# logic-level.net
KiCad netlist of a schematic drawn in EAGLE
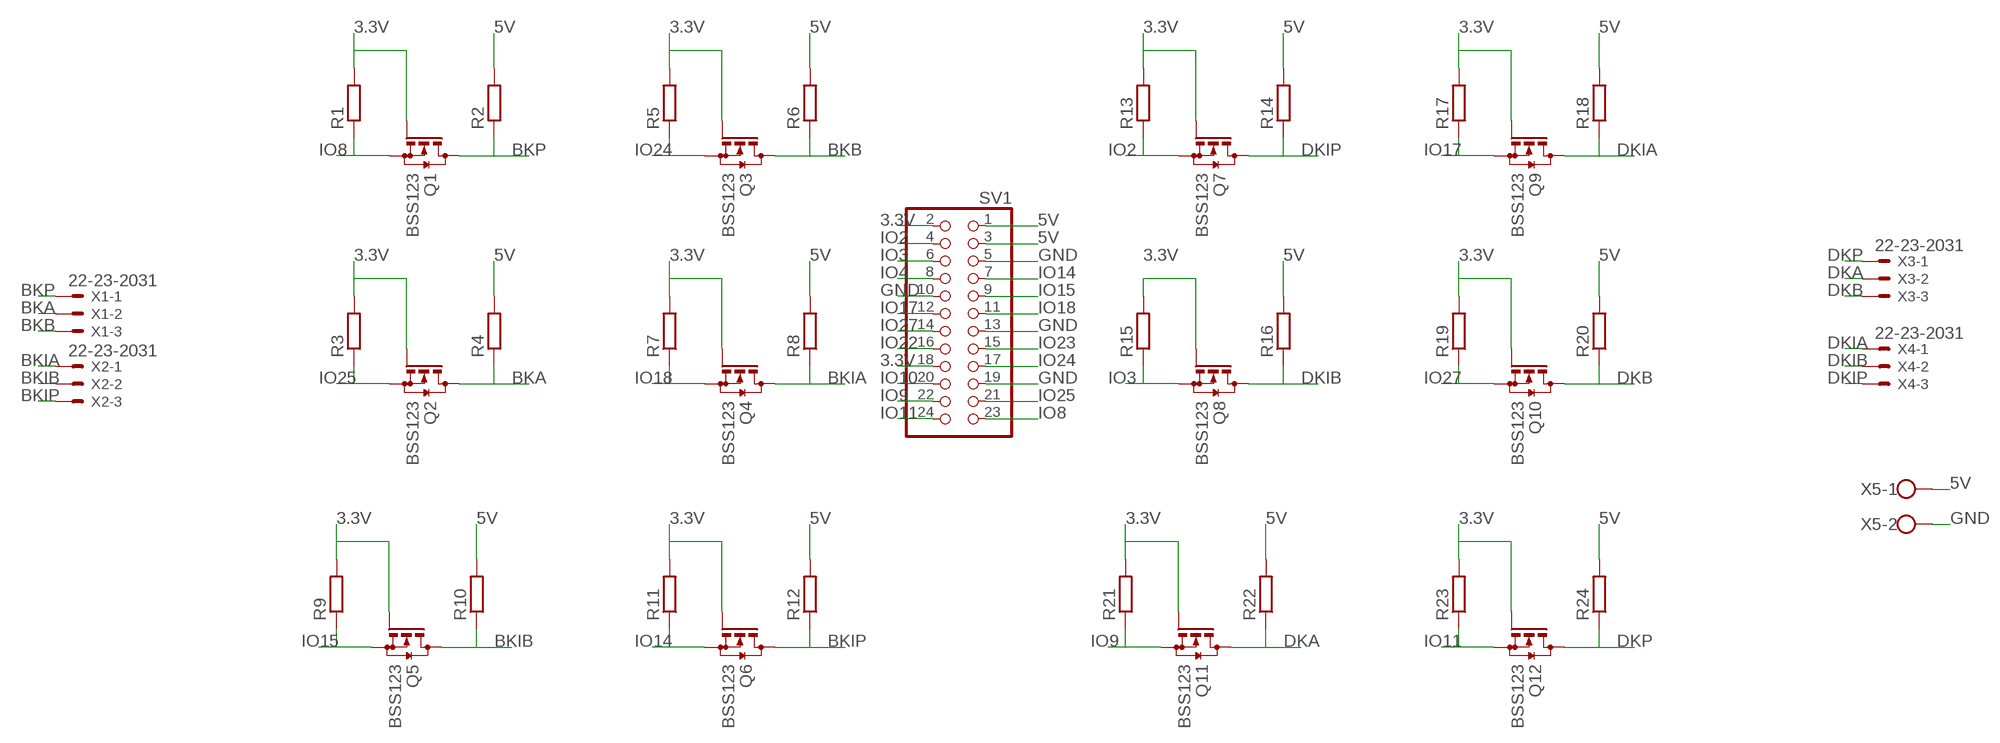
[diagram p0: schematic, sheet 1]

(export (version "E")
  (design (tool "Eeschema 10.0.6"))
  (components
    (comp (ref "Q1")
      (value "BSS123")
      (footprint "eagle-import:SOT23")
      (libsource (lib "eagle-import") (part "BSS123"))
    )
    (comp (ref "Q2")
      (value "BSS123")
      (footprint "eagle-import:SOT23")
      (libsource (lib "eagle-import") (part "BSS123"))
    )
    (comp (ref "Q3")
      (value "BSS123")
      (footprint "eagle-import:SOT23")
      (libsource (lib "eagle-import") (part "BSS123"))
    )
    (comp (ref "Q4")
      (value "BSS123")
      (footprint "eagle-import:SOT23")
      (libsource (lib "eagle-import") (part "BSS123"))
    )
    (comp (ref "Q5")
      (value "BSS123")
      (footprint "eagle-import:SOT23")
      (libsource (lib "eagle-import") (part "BSS123"))
    )
    (comp (ref "Q6")
      (value "BSS123")
      (footprint "eagle-import:SOT23")
      (libsource (lib "eagle-import") (part "BSS123"))
    )
    (comp (ref "Q7")
      (value "BSS123")
      (footprint "eagle-import:SOT23")
      (libsource (lib "eagle-import") (part "BSS123"))
    )
    (comp (ref "Q8")
      (value "BSS123")
      (footprint "eagle-import:SOT23")
      (libsource (lib "eagle-import") (part "BSS123"))
    )
    (comp (ref "Q9")
      (value "BSS123")
      (footprint "eagle-import:SOT23")
      (libsource (lib "eagle-import") (part "BSS123"))
    )
    (comp (ref "Q10")
      (value "BSS123")
      (footprint "eagle-import:SOT23")
      (libsource (lib "eagle-import") (part "BSS123"))
    )
    (comp (ref "Q11")
      (value "BSS123")
      (footprint "eagle-import:SOT23")
      (libsource (lib "eagle-import") (part "BSS123"))
    )
    (comp (ref "Q12")
      (value "BSS123")
      (footprint "eagle-import:SOT23")
      (libsource (lib "eagle-import") (part "BSS123"))
    )
    (comp (ref "R1")
      (value "R-EU_M1206")
      (footprint "eagle-import:M1206")
      (libsource (lib "eagle-import") (part "R-EU_M1206"))
    )
    (comp (ref "R2")
      (value "R-EU_M1206")
      (footprint "eagle-import:M1206")
      (libsource (lib "eagle-import") (part "R-EU_M1206"))
    )
    (comp (ref "R3")
      (value "R-EU_M1206")
      (footprint "eagle-import:M1206")
      (libsource (lib "eagle-import") (part "R-EU_M1206"))
    )
    (comp (ref "R4")
      (value "R-EU_M1206")
      (footprint "eagle-import:M1206")
      (libsource (lib "eagle-import") (part "R-EU_M1206"))
    )
    (comp (ref "R5")
      (value "R-EU_M1206")
      (footprint "eagle-import:M1206")
      (libsource (lib "eagle-import") (part "R-EU_M1206"))
    )
    (comp (ref "R6")
      (value "R-EU_M1206")
      (footprint "eagle-import:M1206")
      (libsource (lib "eagle-import") (part "R-EU_M1206"))
    )
    (comp (ref "R7")
      (value "R-EU_M1206")
      (footprint "eagle-import:M1206")
      (libsource (lib "eagle-import") (part "R-EU_M1206"))
    )
    (comp (ref "R8")
      (value "R-EU_M1206")
      (footprint "eagle-import:M1206")
      (libsource (lib "eagle-import") (part "R-EU_M1206"))
    )
    (comp (ref "R9")
      (value "R-EU_M1206")
      (footprint "eagle-import:M1206")
      (libsource (lib "eagle-import") (part "R-EU_M1206"))
    )
    (comp (ref "R10")
      (value "R-EU_M1206")
      (footprint "eagle-import:M1206")
      (libsource (lib "eagle-import") (part "R-EU_M1206"))
    )
    (comp (ref "R11")
      (value "R-EU_M1206")
      (footprint "eagle-import:M1206")
      (libsource (lib "eagle-import") (part "R-EU_M1206"))
    )
    (comp (ref "R12")
      (value "R-EU_M1206")
      (footprint "eagle-import:M1206")
      (libsource (lib "eagle-import") (part "R-EU_M1206"))
    )
    (comp (ref "R13")
      (value "R-EU_M1206")
      (footprint "eagle-import:M1206")
      (libsource (lib "eagle-import") (part "R-EU_M1206"))
    )
    (comp (ref "R14")
      (value "R-EU_M1206")
      (footprint "eagle-import:M1206")
      (libsource (lib "eagle-import") (part "R-EU_M1206"))
    )
    (comp (ref "R15")
      (value "R-EU_M1206")
      (footprint "eagle-import:M1206")
      (libsource (lib "eagle-import") (part "R-EU_M1206"))
    )
    (comp (ref "R16")
      (value "R-EU_M1206")
      (footprint "eagle-import:M1206")
      (libsource (lib "eagle-import") (part "R-EU_M1206"))
    )
    (comp (ref "R17")
      (value "R-EU_M1206")
      (footprint "eagle-import:M1206")
      (libsource (lib "eagle-import") (part "R-EU_M1206"))
    )
    (comp (ref "R18")
      (value "R-EU_M1206")
      (footprint "eagle-import:M1206")
      (libsource (lib "eagle-import") (part "R-EU_M1206"))
    )
    (comp (ref "R19")
      (value "R-EU_M1206")
      (footprint "eagle-import:M1206")
      (libsource (lib "eagle-import") (part "R-EU_M1206"))
    )
    (comp (ref "R20")
      (value "R-EU_M1206")
      (footprint "eagle-import:M1206")
      (libsource (lib "eagle-import") (part "R-EU_M1206"))
    )
    (comp (ref "R21")
      (value "R-EU_M1206")
      (footprint "eagle-import:M1206")
      (libsource (lib "eagle-import") (part "R-EU_M1206"))
    )
    (comp (ref "R22")
      (value "R-EU_M1206")
      (footprint "eagle-import:M1206")
      (libsource (lib "eagle-import") (part "R-EU_M1206"))
    )
    (comp (ref "R23")
      (value "R-EU_M1206")
      (footprint "eagle-import:M1206")
      (libsource (lib "eagle-import") (part "R-EU_M1206"))
    )
    (comp (ref "R24")
      (value "R-EU_M1206")
      (footprint "eagle-import:M1206")
      (libsource (lib "eagle-import") (part "R-EU_M1206"))
    )
    (comp (ref "SV1")
      (value "PINHD-2X12")
      (footprint "eagle-import:2X12")
      (libsource (lib "eagle-import") (part "PINHD-2X12"))
    )
    (comp (ref "X1")
      (value "22-23-2031")
      (footprint "eagle-import:22-23-2031")
      (fields (field (name "MF") "MOLEX"))
      (libsource (lib "eagle-import") (part "22-23-2031"))
    )
    (comp (ref "X2")
      (value "22-23-2031")
      (footprint "eagle-import:22-23-2031")
      (fields (field (name "MF") "MOLEX"))
      (libsource (lib "eagle-import") (part "22-23-2031"))
    )
    (comp (ref "X3")
      (value "22-23-2031")
      (footprint "eagle-import:22-23-2031")
      (fields (field (name "MF") "MOLEX"))
      (libsource (lib "eagle-import") (part "22-23-2031"))
    )
    (comp (ref "X4")
      (value "22-23-2031")
      (footprint "eagle-import:22-23-2031")
      (fields (field (name "MF") "MOLEX"))
      (libsource (lib "eagle-import") (part "22-23-2031"))
    )
    (comp (ref "X5")
      (value "W237-102")
      (footprint "eagle-import:W237-102")
      (fields (field (name "MPN") "237-102"))
      (libsource (lib "eagle-import") (part "W237-102"))
    )
  )
  (nets
    (net (code "1") (name "/3.3V") (class "Default")
      (node (ref "Q1") (pin "1") (pinfunction "G_1") (pintype "passive"))
      (node (ref "Q10") (pin "1") (pinfunction "G_1") (pintype "passive"))
      (node (ref "Q11") (pin "1") (pinfunction "G_1") (pintype "passive"))
      (node (ref "Q12") (pin "1") (pinfunction "G_1") (pintype "passive"))
      (node (ref "Q2") (pin "1") (pinfunction "G_1") (pintype "passive"))
      (node (ref "Q3") (pin "1") (pinfunction "G_1") (pintype "passive"))
      (node (ref "Q4") (pin "1") (pinfunction "G_1") (pintype "passive"))
      (node (ref "Q5") (pin "1") (pinfunction "G_1") (pintype "passive"))
      (node (ref "Q6") (pin "1") (pinfunction "G_1") (pintype "passive"))
      (node (ref "Q7") (pin "1") (pinfunction "G_1") (pintype "passive"))
      (node (ref "Q8") (pin "1") (pinfunction "G_1") (pintype "passive"))
      (node (ref "Q9") (pin "1") (pinfunction "G_1") (pintype "passive"))
      (node (ref "R1") (pin "2") (pinfunction "2_2") (pintype "passive"))
      (node (ref "R11") (pin "2") (pinfunction "2_2") (pintype "passive"))
      (node (ref "R13") (pin "2") (pinfunction "2_2") (pintype "passive"))
      (node (ref "R15") (pin "2") (pinfunction "2_2") (pintype "passive"))
      (node (ref "R17") (pin "2") (pinfunction "2_2") (pintype "passive"))
      (node (ref "R19") (pin "2") (pinfunction "2_2") (pintype "passive"))
      (node (ref "R21") (pin "2") (pinfunction "2_2") (pintype "passive"))
      (node (ref "R23") (pin "2") (pinfunction "2_2") (pintype "passive"))
      (node (ref "R3") (pin "2") (pinfunction "2_2") (pintype "passive"))
      (node (ref "R5") (pin "2") (pinfunction "2_2") (pintype "passive"))
      (node (ref "R7") (pin "2") (pinfunction "2_2") (pintype "passive"))
      (node (ref "R9") (pin "2") (pinfunction "2_2") (pintype "passive"))
      (node (ref "SV1") (pin "18") (pinfunction "18_18") (pintype "passive"))
      (node (ref "SV1") (pin "2") (pinfunction "2_2") (pintype "passive"))
    )
    (net (code "2") (name "/5V") (class "Default")
      (node (ref "R10") (pin "2") (pinfunction "2_2") (pintype "passive"))
      (node (ref "R12") (pin "2") (pinfunction "2_2") (pintype "passive"))
      (node (ref "R14") (pin "2") (pinfunction "2_2") (pintype "passive"))
      (node (ref "R16") (pin "2") (pinfunction "2_2") (pintype "passive"))
      (node (ref "R18") (pin "2") (pinfunction "2_2") (pintype "passive"))
      (node (ref "R2") (pin "2") (pinfunction "2_2") (pintype "passive"))
      (node (ref "R20") (pin "2") (pinfunction "2_2") (pintype "passive"))
      (node (ref "R22") (pin "2") (pinfunction "2_2") (pintype "passive"))
      (node (ref "R24") (pin "2") (pinfunction "2_2") (pintype "passive"))
      (node (ref "R4") (pin "2") (pinfunction "2_2") (pintype "passive"))
      (node (ref "R6") (pin "2") (pinfunction "2_2") (pintype "passive"))
      (node (ref "R8") (pin "2") (pinfunction "2_2") (pintype "passive"))
      (node (ref "SV1") (pin "1") (pinfunction "1_1") (pintype "passive"))
      (node (ref "SV1") (pin "3") (pinfunction "3_3") (pintype "passive"))
      (node (ref "X5") (pin "1") (pinfunction "KL_1") (pintype "passive"))
    )
    (net (code "3") (name "/BKA") (class "Default")
      (node (ref "Q2") (pin "3") (pinfunction "D_3") (pintype "passive"))
      (node (ref "R4") (pin "1") (pinfunction "1_1") (pintype "passive"))
      (node (ref "X1") (pin "2") (pinfunction "S_2") (pintype "passive"))
    )
    (net (code "4") (name "/BKB") (class "Default")
      (node (ref "Q3") (pin "3") (pinfunction "D_3") (pintype "passive"))
      (node (ref "R6") (pin "1") (pinfunction "1_1") (pintype "passive"))
      (node (ref "X1") (pin "3") (pinfunction "S_3") (pintype "passive"))
    )
    (net (code "5") (name "/BKIA") (class "Default")
      (node (ref "Q4") (pin "3") (pinfunction "D_3") (pintype "passive"))
      (node (ref "R8") (pin "1") (pinfunction "1_1") (pintype "passive"))
      (node (ref "X2") (pin "1") (pinfunction "S_1") (pintype "passive"))
    )
    (net (code "6") (name "/BKIB") (class "Default")
      (node (ref "Q5") (pin "3") (pinfunction "D_3") (pintype "passive"))
      (node (ref "R10") (pin "1") (pinfunction "1_1") (pintype "passive"))
      (node (ref "X2") (pin "2") (pinfunction "S_2") (pintype "passive"))
    )
    (net (code "7") (name "/BKIP") (class "Default")
      (node (ref "Q6") (pin "3") (pinfunction "D_3") (pintype "passive"))
      (node (ref "R12") (pin "1") (pinfunction "1_1") (pintype "passive"))
      (node (ref "X2") (pin "3") (pinfunction "S_3") (pintype "passive"))
    )
    (net (code "8") (name "/BKP") (class "Default")
      (node (ref "Q1") (pin "3") (pinfunction "D_3") (pintype "passive"))
      (node (ref "R2") (pin "1") (pinfunction "1_1") (pintype "passive"))
      (node (ref "X1") (pin "1") (pinfunction "S_1") (pintype "passive"))
    )
    (net (code "9") (name "/DKA") (class "Default")
      (node (ref "Q11") (pin "3") (pinfunction "D_3") (pintype "passive"))
      (node (ref "R22") (pin "1") (pinfunction "1_1") (pintype "passive"))
      (node (ref "X3") (pin "2") (pinfunction "S_2") (pintype "passive"))
    )
    (net (code "10") (name "/DKB") (class "Default")
      (node (ref "Q10") (pin "3") (pinfunction "D_3") (pintype "passive"))
      (node (ref "R20") (pin "1") (pinfunction "1_1") (pintype "passive"))
      (node (ref "X3") (pin "3") (pinfunction "S_3") (pintype "passive"))
    )
    (net (code "11") (name "/DKIA") (class "Default")
      (node (ref "Q9") (pin "3") (pinfunction "D_3") (pintype "passive"))
      (node (ref "R18") (pin "1") (pinfunction "1_1") (pintype "passive"))
      (node (ref "X4") (pin "1") (pinfunction "S_1") (pintype "passive"))
    )
    (net (code "12") (name "/DKIB") (class "Default")
      (node (ref "Q8") (pin "3") (pinfunction "D_3") (pintype "passive"))
      (node (ref "R16") (pin "1") (pinfunction "1_1") (pintype "passive"))
      (node (ref "X4") (pin "2") (pinfunction "S_2") (pintype "passive"))
    )
    (net (code "13") (name "/DKIP") (class "Default")
      (node (ref "Q7") (pin "3") (pinfunction "D_3") (pintype "passive"))
      (node (ref "R14") (pin "1") (pinfunction "1_1") (pintype "passive"))
      (node (ref "X4") (pin "3") (pinfunction "S_3") (pintype "passive"))
    )
    (net (code "14") (name "/DKP") (class "Default")
      (node (ref "Q12") (pin "3") (pinfunction "D_3") (pintype "passive"))
      (node (ref "R24") (pin "1") (pinfunction "1_1") (pintype "passive"))
      (node (ref "X3") (pin "1") (pinfunction "S_1") (pintype "passive"))
    )
    (net (code "15") (name "/GND") (class "Default")
      (node (ref "SV1") (pin "10") (pinfunction "10_10") (pintype "passive"))
      (node (ref "SV1") (pin "13") (pinfunction "13_13") (pintype "passive"))
      (node (ref "SV1") (pin "19") (pinfunction "19_19") (pintype "passive"))
      (node (ref "SV1") (pin "5") (pinfunction "5_5") (pintype "passive"))
      (node (ref "X5") (pin "2") (pinfunction "KL_2") (pintype "passive"))
    )
    (net (code "16") (name "/IO2") (class "Default")
      (node (ref "Q7") (pin "2") (pinfunction "S_2") (pintype "passive"))
      (node (ref "R13") (pin "1") (pinfunction "1_1") (pintype "passive"))
      (node (ref "SV1") (pin "4") (pinfunction "4_4") (pintype "passive"))
    )
    (net (code "17") (name "/IO3") (class "Default")
      (node (ref "Q8") (pin "2") (pinfunction "S_2") (pintype "passive"))
      (node (ref "R15") (pin "1") (pinfunction "1_1") (pintype "passive"))
      (node (ref "SV1") (pin "6") (pinfunction "6_6") (pintype "passive"))
    )
    (net (code "18") (name "/IO4") (class "Default")
      (node (ref "SV1") (pin "8") (pinfunction "8_8") (pintype "passive"))
    )
    (net (code "19") (name "/IO8") (class "Default")
      (node (ref "Q1") (pin "2") (pinfunction "S_2") (pintype "passive"))
      (node (ref "R1") (pin "1") (pinfunction "1_1") (pintype "passive"))
      (node (ref "SV1") (pin "23") (pinfunction "23_23") (pintype "passive"))
    )
    (net (code "20") (name "/IO9") (class "Default")
      (node (ref "Q11") (pin "2") (pinfunction "S_2") (pintype "passive"))
      (node (ref "R21") (pin "1") (pinfunction "1_1") (pintype "passive"))
      (node (ref "SV1") (pin "22") (pinfunction "22_22") (pintype "passive"))
    )
    (net (code "21") (name "/IO10") (class "Default")
      (node (ref "SV1") (pin "20") (pinfunction "20_20") (pintype "passive"))
    )
    (net (code "22") (name "/IO11") (class "Default")
      (node (ref "Q12") (pin "2") (pinfunction "S_2") (pintype "passive"))
      (node (ref "R23") (pin "1") (pinfunction "1_1") (pintype "passive"))
      (node (ref "SV1") (pin "24") (pinfunction "24_24") (pintype "passive"))
    )
    (net (code "23") (name "/IO14") (class "Default")
      (node (ref "Q6") (pin "2") (pinfunction "S_2") (pintype "passive"))
      (node (ref "R11") (pin "1") (pinfunction "1_1") (pintype "passive"))
      (node (ref "SV1") (pin "7") (pinfunction "7_7") (pintype "passive"))
    )
    (net (code "24") (name "/IO15") (class "Default")
      (node (ref "Q5") (pin "2") (pinfunction "S_2") (pintype "passive"))
      (node (ref "R9") (pin "1") (pinfunction "1_1") (pintype "passive"))
      (node (ref "SV1") (pin "9") (pinfunction "9_9") (pintype "passive"))
    )
    (net (code "25") (name "/IO17") (class "Default")
      (node (ref "Q9") (pin "2") (pinfunction "S_2") (pintype "passive"))
      (node (ref "R17") (pin "1") (pinfunction "1_1") (pintype "passive"))
      (node (ref "SV1") (pin "12") (pinfunction "12_12") (pintype "passive"))
    )
    (net (code "26") (name "/IO18") (class "Default")
      (node (ref "Q4") (pin "2") (pinfunction "S_2") (pintype "passive"))
      (node (ref "R7") (pin "1") (pinfunction "1_1") (pintype "passive"))
      (node (ref "SV1") (pin "11") (pinfunction "11_11") (pintype "passive"))
    )
    (net (code "27") (name "/IO22") (class "Default")
      (node (ref "SV1") (pin "16") (pinfunction "16_16") (pintype "passive"))
    )
    (net (code "28") (name "/IO23") (class "Default")
      (node (ref "SV1") (pin "15") (pinfunction "15_15") (pintype "passive"))
    )
    (net (code "29") (name "/IO24") (class "Default")
      (node (ref "Q3") (pin "2") (pinfunction "S_2") (pintype "passive"))
      (node (ref "R5") (pin "1") (pinfunction "1_1") (pintype "passive"))
      (node (ref "SV1") (pin "17") (pinfunction "17_17") (pintype "passive"))
    )
    (net (code "30") (name "/IO25") (class "Default")
      (node (ref "Q2") (pin "2") (pinfunction "S_2") (pintype "passive"))
      (node (ref "R3") (pin "1") (pinfunction "1_1") (pintype "passive"))
      (node (ref "SV1") (pin "21") (pinfunction "21_21") (pintype "passive"))
    )
    (net (code "31") (name "/IO27") (class "Default")
      (node (ref "Q10") (pin "2") (pinfunction "S_2") (pintype "passive"))
      (node (ref "R19") (pin "1") (pinfunction "1_1") (pintype "passive"))
      (node (ref "SV1") (pin "14") (pinfunction "14_14") (pintype "passive"))
    )
  )
)
